# trasmissores_e_receptores.net
KiCad netlist of a schematic drawn in Altium Designer
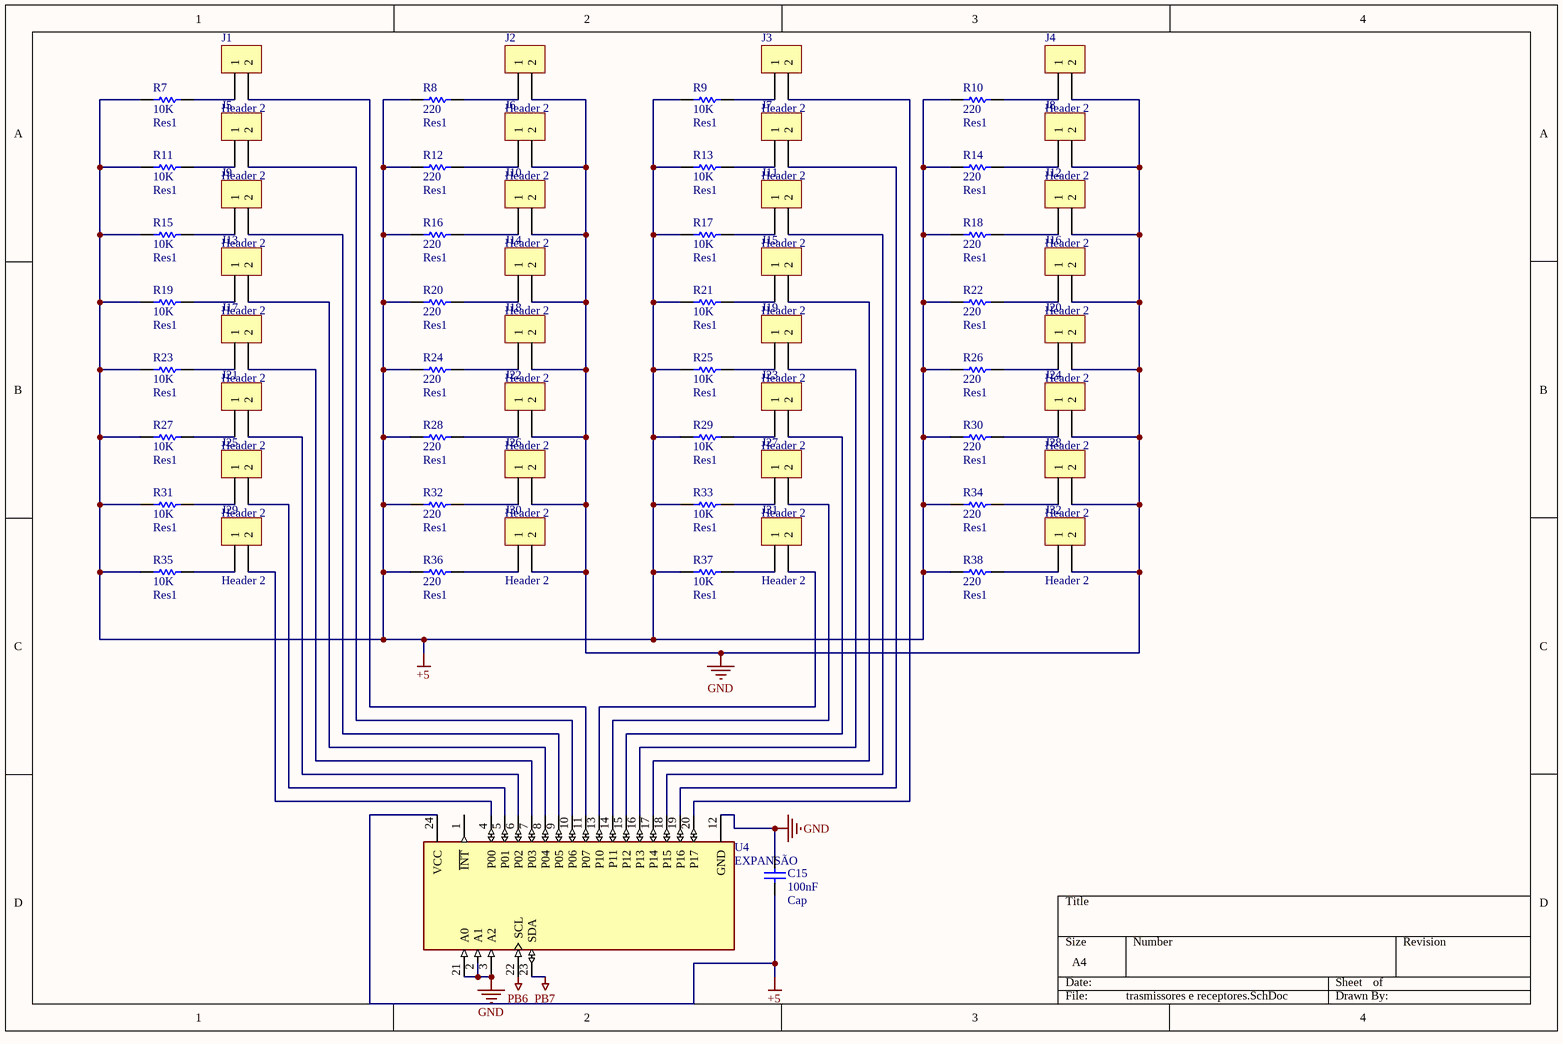
[diagram p0: trasmissores e receptores.SchDoc]

(export (version "E")
  (design (tool "Eeschema 10.0.6"))
  (components
    (comp (ref "C15")
      (value "Cap")
      (footprint "lib_footprint_projeto:CAP100N")
      (description "Capacitor")
      (fields (field (name "ALTIUM_VALUE") "100nF") (field (name "PUBLISHER") "Altium Limited"))
      (libsource (lib "Miscellaneous Devices") (part "Cap"))
    )
    (comp (ref "J1")
      (value "Header 2")
      (footprint "lib_footprint_projeto:Header_KK_2vias")
      (description "Conn KK 2 vias")
      (fields (field (name "PUBLISHER") "Altium Limited"))
      (libsource (lib "projeto_pi_3b") (part "Header 2"))
    )
    (comp (ref "J2")
      (value "Header 2")
      (footprint "lib_footprint_projeto:Header_KK_2vias")
      (description "Conn KK 2 vias")
      (fields (field (name "PUBLISHER") "Altium Limited"))
      (libsource (lib "projeto_pi_3b") (part "Header 2"))
    )
    (comp (ref "J3")
      (value "Header 2")
      (footprint "lib_footprint_projeto:Header_KK_2vias")
      (description "Conn KK 2 vias")
      (fields (field (name "PUBLISHER") "Altium Limited"))
      (libsource (lib "projeto_pi_3b") (part "Header 2"))
    )
    (comp (ref "J4")
      (value "Header 2")
      (footprint "lib_footprint_projeto:Header_KK_2vias")
      (description "Conn KK 2 vias")
      (fields (field (name "PUBLISHER") "Altium Limited"))
      (libsource (lib "projeto_pi_3b") (part "Header 2"))
    )
    (comp (ref "J5")
      (value "Header 2")
      (footprint "lib_footprint_projeto:Header_KK_2vias")
      (description "Conn KK 2 vias")
      (fields (field (name "PUBLISHER") "Altium Limited"))
      (libsource (lib "projeto_pi_3b") (part "Header 2"))
    )
    (comp (ref "J6")
      (value "Header 2")
      (footprint "lib_footprint_projeto:Header_KK_2vias")
      (description "Conn KK 2 vias")
      (fields (field (name "PUBLISHER") "Altium Limited"))
      (libsource (lib "projeto_pi_3b") (part "Header 2"))
    )
    (comp (ref "J7")
      (value "Header 2")
      (footprint "lib_footprint_projeto:Header_KK_2vias")
      (description "Conn KK 2 vias")
      (fields (field (name "PUBLISHER") "Altium Limited"))
      (libsource (lib "projeto_pi_3b") (part "Header 2"))
    )
    (comp (ref "J8")
      (value "Header 2")
      (footprint "lib_footprint_projeto:Header_KK_2vias")
      (description "Conn KK 2 vias")
      (fields (field (name "PUBLISHER") "Altium Limited"))
      (libsource (lib "projeto_pi_3b") (part "Header 2"))
    )
    (comp (ref "J9")
      (value "Header 2")
      (footprint "lib_footprint_projeto:Header_KK_2vias")
      (description "Conn KK 2 vias")
      (fields (field (name "PUBLISHER") "Altium Limited"))
      (libsource (lib "projeto_pi_3b") (part "Header 2"))
    )
    (comp (ref "J10")
      (value "Header 2")
      (footprint "lib_footprint_projeto:Header_KK_2vias")
      (description "Conn KK 2 vias")
      (fields (field (name "PUBLISHER") "Altium Limited"))
      (libsource (lib "projeto_pi_3b") (part "Header 2"))
    )
    (comp (ref "J11")
      (value "Header 2")
      (footprint "lib_footprint_projeto:Header_KK_2vias")
      (description "Conn KK 2 vias")
      (fields (field (name "PUBLISHER") "Altium Limited"))
      (libsource (lib "projeto_pi_3b") (part "Header 2"))
    )
    (comp (ref "J12")
      (value "Header 2")
      (footprint "lib_footprint_projeto:Header_KK_2vias")
      (description "Conn KK 2 vias")
      (fields (field (name "PUBLISHER") "Altium Limited"))
      (libsource (lib "projeto_pi_3b") (part "Header 2"))
    )
    (comp (ref "J13")
      (value "Header 2")
      (footprint "lib_footprint_projeto:Header_KK_2vias")
      (description "Conn KK 2 vias")
      (fields (field (name "PUBLISHER") "Altium Limited"))
      (libsource (lib "projeto_pi_3b") (part "Header 2"))
    )
    (comp (ref "J14")
      (value "Header 2")
      (footprint "lib_footprint_projeto:Header_KK_2vias")
      (description "Conn KK 2 vias")
      (fields (field (name "PUBLISHER") "Altium Limited"))
      (libsource (lib "projeto_pi_3b") (part "Header 2"))
    )
    (comp (ref "J15")
      (value "Header 2")
      (footprint "lib_footprint_projeto:Header_KK_2vias")
      (description "Conn KK 2 vias")
      (fields (field (name "PUBLISHER") "Altium Limited"))
      (libsource (lib "projeto_pi_3b") (part "Header 2"))
    )
    (comp (ref "J16")
      (value "Header 2")
      (footprint "lib_footprint_projeto:Header_KK_2vias")
      (description "Conn KK 2 vias")
      (fields (field (name "PUBLISHER") "Altium Limited"))
      (libsource (lib "projeto_pi_3b") (part "Header 2"))
    )
    (comp (ref "J17")
      (value "Header 2")
      (footprint "lib_footprint_projeto:Header_KK_2vias")
      (description "Conn KK 2 vias")
      (fields (field (name "PUBLISHER") "Altium Limited"))
      (libsource (lib "projeto_pi_3b") (part "Header 2"))
    )
    (comp (ref "J18")
      (value "Header 2")
      (footprint "lib_footprint_projeto:Header_KK_2vias")
      (description "Conn KK 2 vias")
      (fields (field (name "PUBLISHER") "Altium Limited"))
      (libsource (lib "projeto_pi_3b") (part "Header 2"))
    )
    (comp (ref "J19")
      (value "Header 2")
      (footprint "lib_footprint_projeto:Header_KK_2vias")
      (description "Conn KK 2 vias")
      (fields (field (name "PUBLISHER") "Altium Limited"))
      (libsource (lib "projeto_pi_3b") (part "Header 2"))
    )
    (comp (ref "J20")
      (value "Header 2")
      (footprint "lib_footprint_projeto:Header_KK_2vias")
      (description "Conn KK 2 vias")
      (fields (field (name "PUBLISHER") "Altium Limited"))
      (libsource (lib "projeto_pi_3b") (part "Header 2"))
    )
    (comp (ref "J21")
      (value "Header 2")
      (footprint "lib_footprint_projeto:Header_KK_2vias")
      (description "Conn KK 2 vias")
      (fields (field (name "PUBLISHER") "Altium Limited"))
      (libsource (lib "projeto_pi_3b") (part "Header 2"))
    )
    (comp (ref "J22")
      (value "Header 2")
      (footprint "lib_footprint_projeto:Header_KK_2vias")
      (description "Conn KK 2 vias")
      (fields (field (name "PUBLISHER") "Altium Limited"))
      (libsource (lib "projeto_pi_3b") (part "Header 2"))
    )
    (comp (ref "J23")
      (value "Header 2")
      (footprint "lib_footprint_projeto:Header_KK_2vias")
      (description "Conn KK 2 vias")
      (fields (field (name "PUBLISHER") "Altium Limited"))
      (libsource (lib "projeto_pi_3b") (part "Header 2"))
    )
    (comp (ref "J24")
      (value "Header 2")
      (footprint "lib_footprint_projeto:Header_KK_2vias")
      (description "Conn KK 2 vias")
      (fields (field (name "PUBLISHER") "Altium Limited"))
      (libsource (lib "projeto_pi_3b") (part "Header 2"))
    )
    (comp (ref "J25")
      (value "Header 2")
      (footprint "lib_footprint_projeto:Header_KK_2vias")
      (description "Conn KK 2 vias")
      (fields (field (name "PUBLISHER") "Altium Limited"))
      (libsource (lib "projeto_pi_3b") (part "Header 2"))
    )
    (comp (ref "J26")
      (value "Header 2")
      (footprint "lib_footprint_projeto:Header_KK_2vias")
      (description "Conn KK 2 vias")
      (fields (field (name "PUBLISHER") "Altium Limited"))
      (libsource (lib "projeto_pi_3b") (part "Header 2"))
    )
    (comp (ref "J27")
      (value "Header 2")
      (footprint "lib_footprint_projeto:Header_KK_2vias")
      (description "Conn KK 2 vias")
      (fields (field (name "PUBLISHER") "Altium Limited"))
      (libsource (lib "projeto_pi_3b") (part "Header 2"))
    )
    (comp (ref "J28")
      (value "Header 2")
      (footprint "lib_footprint_projeto:Header_KK_2vias")
      (description "Conn KK 2 vias")
      (fields (field (name "PUBLISHER") "Altium Limited"))
      (libsource (lib "projeto_pi_3b") (part "Header 2"))
    )
    (comp (ref "J29")
      (value "Header 2")
      (footprint "lib_footprint_projeto:Header_KK_2vias")
      (description "Conn KK 2 vias")
      (fields (field (name "PUBLISHER") "Altium Limited"))
      (libsource (lib "projeto_pi_3b") (part "Header 2"))
    )
    (comp (ref "J30")
      (value "Header 2")
      (footprint "lib_footprint_projeto:Header_KK_2vias")
      (description "Conn KK 2 vias")
      (fields (field (name "PUBLISHER") "Altium Limited"))
      (libsource (lib "projeto_pi_3b") (part "Header 2"))
    )
    (comp (ref "J31")
      (value "Header 2")
      (footprint "lib_footprint_projeto:Header_KK_2vias")
      (description "Conn KK 2 vias")
      (fields (field (name "PUBLISHER") "Altium Limited"))
      (libsource (lib "projeto_pi_3b") (part "Header 2"))
    )
    (comp (ref "J32")
      (value "Header 2")
      (footprint "lib_footprint_projeto:Header_KK_2vias")
      (description "Conn KK 2 vias")
      (fields (field (name "PUBLISHER") "Altium Limited"))
      (libsource (lib "projeto_pi_3b") (part "Header 2"))
    )
    (comp (ref "R7")
      (value "Res1")
      (footprint "lib_footprint_projeto:RES10K")
      (description "Resistor")
      (fields (field (name "ALTIUM_VALUE") "10K") (field (name "PUBLISHER") "Altium Limited"))
      (libsource (lib "Miscellaneous Devices") (part "Res1"))
    )
    (comp (ref "R8")
      (value "Res1")
      (footprint "lib_footprint_projeto:RES220")
      (description "Resistor")
      (fields (field (name "ALTIUM_VALUE") "220") (field (name "PUBLISHER") "Altium Limited"))
      (libsource (lib "Miscellaneous Devices") (part "Res1"))
    )
    (comp (ref "R9")
      (value "Res1")
      (footprint "lib_footprint_projeto:RES10K")
      (description "Resistor")
      (fields (field (name "ALTIUM_VALUE") "10K") (field (name "PUBLISHER") "Altium Limited"))
      (libsource (lib "Miscellaneous Devices") (part "Res1"))
    )
    (comp (ref "R10")
      (value "Res1")
      (footprint "lib_footprint_projeto:RES220")
      (description "Resistor")
      (fields (field (name "ALTIUM_VALUE") "220") (field (name "PUBLISHER") "Altium Limited"))
      (libsource (lib "Miscellaneous Devices") (part "Res1"))
    )
    (comp (ref "R11")
      (value "Res1")
      (footprint "lib_footprint_projeto:RES10K")
      (description "Resistor")
      (fields (field (name "ALTIUM_VALUE") "10K") (field (name "PUBLISHER") "Altium Limited"))
      (libsource (lib "Miscellaneous Devices") (part "Res1"))
    )
    (comp (ref "R12")
      (value "Res1")
      (footprint "lib_footprint_projeto:RES220")
      (description "Resistor")
      (fields (field (name "ALTIUM_VALUE") "220") (field (name "PUBLISHER") "Altium Limited"))
      (libsource (lib "Miscellaneous Devices") (part "Res1"))
    )
    (comp (ref "R13")
      (value "Res1")
      (footprint "lib_footprint_projeto:RES10K")
      (description "Resistor")
      (fields (field (name "ALTIUM_VALUE") "10K") (field (name "PUBLISHER") "Altium Limited"))
      (libsource (lib "Miscellaneous Devices") (part "Res1"))
    )
    (comp (ref "R14")
      (value "Res1")
      (footprint "lib_footprint_projeto:RES220")
      (description "Resistor")
      (fields (field (name "ALTIUM_VALUE") "220") (field (name "PUBLISHER") "Altium Limited"))
      (libsource (lib "Miscellaneous Devices") (part "Res1"))
    )
    (comp (ref "R15")
      (value "Res1")
      (footprint "lib_footprint_projeto:RES10K")
      (description "Resistor")
      (fields (field (name "ALTIUM_VALUE") "10K") (field (name "PUBLISHER") "Altium Limited"))
      (libsource (lib "Miscellaneous Devices") (part "Res1"))
    )
    (comp (ref "R16")
      (value "Res1")
      (footprint "lib_footprint_projeto:RES220")
      (description "Resistor")
      (fields (field (name "ALTIUM_VALUE") "220") (field (name "PUBLISHER") "Altium Limited"))
      (libsource (lib "Miscellaneous Devices") (part "Res1"))
    )
    (comp (ref "R17")
      (value "Res1")
      (footprint "lib_footprint_projeto:RES10K")
      (description "Resistor")
      (fields (field (name "ALTIUM_VALUE") "10K") (field (name "PUBLISHER") "Altium Limited"))
      (libsource (lib "Miscellaneous Devices") (part "Res1"))
    )
    (comp (ref "R18")
      (value "Res1")
      (footprint "lib_footprint_projeto:RES220")
      (description "Resistor")
      (fields (field (name "ALTIUM_VALUE") "220") (field (name "PUBLISHER") "Altium Limited"))
      (libsource (lib "Miscellaneous Devices") (part "Res1"))
    )
    (comp (ref "R19")
      (value "Res1")
      (footprint "lib_footprint_projeto:RES10K")
      (description "Resistor")
      (fields (field (name "ALTIUM_VALUE") "10K") (field (name "PUBLISHER") "Altium Limited"))
      (libsource (lib "Miscellaneous Devices") (part "Res1"))
    )
    (comp (ref "R20")
      (value "Res1")
      (footprint "lib_footprint_projeto:RES220")
      (description "Resistor")
      (fields (field (name "ALTIUM_VALUE") "220") (field (name "PUBLISHER") "Altium Limited"))
      (libsource (lib "Miscellaneous Devices") (part "Res1"))
    )
    (comp (ref "R21")
      (value "Res1")
      (footprint "lib_footprint_projeto:RES10K")
      (description "Resistor")
      (fields (field (name "ALTIUM_VALUE") "10K") (field (name "PUBLISHER") "Altium Limited"))
      (libsource (lib "Miscellaneous Devices") (part "Res1"))
    )
    (comp (ref "R22")
      (value "Res1")
      (footprint "lib_footprint_projeto:RES220")
      (description "Resistor")
      (fields (field (name "ALTIUM_VALUE") "220") (field (name "PUBLISHER") "Altium Limited"))
      (libsource (lib "Miscellaneous Devices") (part "Res1"))
    )
    (comp (ref "R23")
      (value "Res1")
      (footprint "lib_footprint_projeto:RES10K")
      (description "Resistor")
      (fields (field (name "ALTIUM_VALUE") "10K") (field (name "PUBLISHER") "Altium Limited"))
      (libsource (lib "Miscellaneous Devices") (part "Res1"))
    )
    (comp (ref "R24")
      (value "Res1")
      (footprint "lib_footprint_projeto:RES220")
      (description "Resistor")
      (fields (field (name "ALTIUM_VALUE") "220") (field (name "PUBLISHER") "Altium Limited"))
      (libsource (lib "Miscellaneous Devices") (part "Res1"))
    )
    (comp (ref "R25")
      (value "Res1")
      (footprint "lib_footprint_projeto:RES10K")
      (description "Resistor")
      (fields (field (name "ALTIUM_VALUE") "10K") (field (name "PUBLISHER") "Altium Limited"))
      (libsource (lib "Miscellaneous Devices") (part "Res1"))
    )
    (comp (ref "R26")
      (value "Res1")
      (footprint "lib_footprint_projeto:RES220")
      (description "Resistor")
      (fields (field (name "ALTIUM_VALUE") "220") (field (name "PUBLISHER") "Altium Limited"))
      (libsource (lib "Miscellaneous Devices") (part "Res1"))
    )
    (comp (ref "R27")
      (value "Res1")
      (footprint "lib_footprint_projeto:RES10K")
      (description "Resistor")
      (fields (field (name "ALTIUM_VALUE") "10K") (field (name "PUBLISHER") "Altium Limited"))
      (libsource (lib "Miscellaneous Devices") (part "Res1"))
    )
    (comp (ref "R28")
      (value "Res1")
      (footprint "lib_footprint_projeto:RES220")
      (description "Resistor")
      (fields (field (name "ALTIUM_VALUE") "220") (field (name "PUBLISHER") "Altium Limited"))
      (libsource (lib "Miscellaneous Devices") (part "Res1"))
    )
    (comp (ref "R29")
      (value "Res1")
      (footprint "lib_footprint_projeto:RES10K")
      (description "Resistor")
      (fields (field (name "ALTIUM_VALUE") "10K") (field (name "PUBLISHER") "Altium Limited"))
      (libsource (lib "Miscellaneous Devices") (part "Res1"))
    )
    (comp (ref "R30")
      (value "Res1")
      (footprint "lib_footprint_projeto:RES220")
      (description "Resistor")
      (fields (field (name "ALTIUM_VALUE") "220") (field (name "PUBLISHER") "Altium Limited"))
      (libsource (lib "Miscellaneous Devices") (part "Res1"))
    )
    (comp (ref "R31")
      (value "Res1")
      (footprint "lib_footprint_projeto:RES10K")
      (description "Resistor")
      (fields (field (name "ALTIUM_VALUE") "10K") (field (name "PUBLISHER") "Altium Limited"))
      (libsource (lib "Miscellaneous Devices") (part "Res1"))
    )
    (comp (ref "R32")
      (value "Res1")
      (footprint "lib_footprint_projeto:RES220")
      (description "Resistor")
      (fields (field (name "ALTIUM_VALUE") "220") (field (name "PUBLISHER") "Altium Limited"))
      (libsource (lib "Miscellaneous Devices") (part "Res1"))
    )
    (comp (ref "R33")
      (value "Res1")
      (footprint "lib_footprint_projeto:RES10K")
      (description "Resistor")
      (fields (field (name "ALTIUM_VALUE") "10K") (field (name "PUBLISHER") "Altium Limited"))
      (libsource (lib "Miscellaneous Devices") (part "Res1"))
    )
    (comp (ref "R34")
      (value "Res1")
      (footprint "lib_footprint_projeto:RES220")
      (description "Resistor")
      (fields (field (name "ALTIUM_VALUE") "220") (field (name "PUBLISHER") "Altium Limited"))
      (libsource (lib "Miscellaneous Devices") (part "Res1"))
    )
    (comp (ref "R35")
      (value "Res1")
      (footprint "lib_footprint_projeto:RES10K")
      (description "Resistor")
      (fields (field (name "ALTIUM_VALUE") "10K") (field (name "PUBLISHER") "Altium Limited"))
      (libsource (lib "Miscellaneous Devices") (part "Res1"))
    )
    (comp (ref "R36")
      (value "Res1")
      (footprint "lib_footprint_projeto:RES220")
      (description "Resistor")
      (fields (field (name "ALTIUM_VALUE") "220") (field (name "PUBLISHER") "Altium Limited"))
      (libsource (lib "Miscellaneous Devices") (part "Res1"))
    )
    (comp (ref "R37")
      (value "Res1")
      (footprint "lib_footprint_projeto:RES10K")
      (description "Resistor")
      (fields (field (name "ALTIUM_VALUE") "10K") (field (name "PUBLISHER") "Altium Limited"))
      (libsource (lib "Miscellaneous Devices") (part "Res1"))
    )
    (comp (ref "R38")
      (value "Res1")
      (footprint "lib_footprint_projeto:RES220")
      (description "Resistor")
      (fields (field (name "ALTIUM_VALUE") "220") (field (name "PUBLISHER") "Altium Limited"))
      (libsource (lib "Miscellaneous Devices") (part "Res1"))
    )
    (comp (ref "U4")
      (value "EXPANSÃO")
      (footprint "lib_footprint_projeto:Modulo")
      (description "16-bit 2.5- to 5.5-V I2C/SMBus I/O expander with interrupt")
      (fields (field (name "MF") "Texas Instruments") (field (name "MP") "PCF8575DW"))
      (libsource (lib "projeto_pi_3b") (part "EXPANSÃO"))
    )
  )
  (nets
    (net (code "1") (name "+5") (class "Default")
      (node (ref "C15") (pin "1") (pinfunction "1_1") (pintype "passive"))
      (node (ref "R10") (pin "1") (pinfunction "1_1") (pintype "passive"))
      (node (ref "R11") (pin "1") (pinfunction "1_1") (pintype "passive"))
      (node (ref "R12") (pin "1") (pinfunction "1_1") (pintype "passive"))
      (node (ref "R13") (pin "1") (pinfunction "1_1") (pintype "passive"))
      (node (ref "R14") (pin "1") (pinfunction "1_1") (pintype "passive"))
      (node (ref "R15") (pin "1") (pinfunction "1_1") (pintype "passive"))
      (node (ref "R16") (pin "1") (pinfunction "1_1") (pintype "passive"))
      (node (ref "R17") (pin "1") (pinfunction "1_1") (pintype "passive"))
      (node (ref "R18") (pin "1") (pinfunction "1_1") (pintype "passive"))
      (node (ref "R19") (pin "1") (pinfunction "1_1") (pintype "passive"))
      (node (ref "R20") (pin "1") (pinfunction "1_1") (pintype "passive"))
      (node (ref "R21") (pin "1") (pinfunction "1_1") (pintype "passive"))
      (node (ref "R22") (pin "1") (pinfunction "1_1") (pintype "passive"))
      (node (ref "R23") (pin "1") (pinfunction "1_1") (pintype "passive"))
      (node (ref "R24") (pin "1") (pinfunction "1_1") (pintype "passive"))
      (node (ref "R25") (pin "1") (pinfunction "1_1") (pintype "passive"))
      (node (ref "R26") (pin "1") (pinfunction "1_1") (pintype "passive"))
      (node (ref "R27") (pin "1") (pinfunction "1_1") (pintype "passive"))
      (node (ref "R28") (pin "1") (pinfunction "1_1") (pintype "passive"))
      (node (ref "R29") (pin "1") (pinfunction "1_1") (pintype "passive"))
      (node (ref "R30") (pin "1") (pinfunction "1_1") (pintype "passive"))
      (node (ref "R31") (pin "1") (pinfunction "1_1") (pintype "passive"))
      (node (ref "R32") (pin "1") (pinfunction "1_1") (pintype "passive"))
      (node (ref "R33") (pin "1") (pinfunction "1_1") (pintype "passive"))
      (node (ref "R34") (pin "1") (pinfunction "1_1") (pintype "passive"))
      (node (ref "R35") (pin "1") (pinfunction "1_1") (pintype "passive"))
      (node (ref "R36") (pin "1") (pinfunction "1_1") (pintype "passive"))
      (node (ref "R37") (pin "1") (pinfunction "1_1") (pintype "passive"))
      (node (ref "R38") (pin "1") (pinfunction "1_1") (pintype "passive"))
      (node (ref "R7") (pin "1") (pinfunction "1_1") (pintype "passive"))
      (node (ref "R8") (pin "1") (pinfunction "1_1") (pintype "passive"))
      (node (ref "R9") (pin "1") (pinfunction "1_1") (pintype "passive"))
      (node (ref "U4") (pin "24") (pinfunction "VCC_24") (pintype "power_in"))
    )
    (net (code "2") (name "GND") (class "Default")
      (node (ref "C15") (pin "2") (pinfunction "2_2") (pintype "passive"))
      (node (ref "J10") (pin "2") (pinfunction "2_2") (pintype "passive"))
      (node (ref "J12") (pin "2") (pinfunction "2_2") (pintype "passive"))
      (node (ref "J14") (pin "2") (pinfunction "2_2") (pintype "passive"))
      (node (ref "J16") (pin "2") (pinfunction "2_2") (pintype "passive"))
      (node (ref "J18") (pin "2") (pinfunction "2_2") (pintype "passive"))
      (node (ref "J2") (pin "2") (pinfunction "2_2") (pintype "passive"))
      (node (ref "J20") (pin "2") (pinfunction "2_2") (pintype "passive"))
      (node (ref "J22") (pin "2") (pinfunction "2_2") (pintype "passive"))
      (node (ref "J24") (pin "2") (pinfunction "2_2") (pintype "passive"))
      (node (ref "J26") (pin "2") (pinfunction "2_2") (pintype "passive"))
      (node (ref "J28") (pin "2") (pinfunction "2_2") (pintype "passive"))
      (node (ref "J30") (pin "2") (pinfunction "2_2") (pintype "passive"))
      (node (ref "J32") (pin "2") (pinfunction "2_2") (pintype "passive"))
      (node (ref "J4") (pin "2") (pinfunction "2_2") (pintype "passive"))
      (node (ref "J6") (pin "2") (pinfunction "2_2") (pintype "passive"))
      (node (ref "J8") (pin "2") (pinfunction "2_2") (pintype "passive"))
      (node (ref "U4") (pin "12") (pinfunction "GND_12") (pintype "power_in"))
      (node (ref "U4") (pin "2") (pinfunction "A1_2") (pintype "input"))
      (node (ref "U4") (pin "21") (pinfunction "A0_21") (pintype "input"))
      (node (ref "U4") (pin "3") (pinfunction "A2_3") (pintype "input"))
    )
    (net (code "3") (name "Net-(J1-Pad1)") (class "Default")
      (node (ref "J1") (pin "1") (pinfunction "1_1") (pintype "passive"))
      (node (ref "R7") (pin "2") (pinfunction "2_2") (pintype "passive"))
    )
    (net (code "4") (name "Net-(J2-Pad1)") (class "Default")
      (node (ref "J2") (pin "1") (pinfunction "1_1") (pintype "passive"))
      (node (ref "R8") (pin "2") (pinfunction "2_2") (pintype "passive"))
    )
    (net (code "5") (name "Net-(J3-Pad1)") (class "Default")
      (node (ref "J3") (pin "1") (pinfunction "1_1") (pintype "passive"))
      (node (ref "R9") (pin "2") (pinfunction "2_2") (pintype "passive"))
    )
    (net (code "6") (name "Net-(J4-Pad1)") (class "Default")
      (node (ref "J4") (pin "1") (pinfunction "1_1") (pintype "passive"))
      (node (ref "R10") (pin "2") (pinfunction "2_2") (pintype "passive"))
    )
    (net (code "7") (name "Net-(J5-Pad1)") (class "Default")
      (node (ref "J5") (pin "1") (pinfunction "1_1") (pintype "passive"))
      (node (ref "R11") (pin "2") (pinfunction "2_2") (pintype "passive"))
    )
    (net (code "8") (name "Net-(J6-Pad1)") (class "Default")
      (node (ref "J6") (pin "1") (pinfunction "1_1") (pintype "passive"))
      (node (ref "R12") (pin "2") (pinfunction "2_2") (pintype "passive"))
    )
    (net (code "9") (name "Net-(J7-Pad1)") (class "Default")
      (node (ref "J7") (pin "1") (pinfunction "1_1") (pintype "passive"))
      (node (ref "R13") (pin "2") (pinfunction "2_2") (pintype "passive"))
    )
    (net (code "10") (name "Net-(J8-Pad1)") (class "Default")
      (node (ref "J8") (pin "1") (pinfunction "1_1") (pintype "passive"))
      (node (ref "R14") (pin "2") (pinfunction "2_2") (pintype "passive"))
    )
    (net (code "11") (name "Net-(J9-Pad1)") (class "Default")
      (node (ref "J9") (pin "1") (pinfunction "1_1") (pintype "passive"))
      (node (ref "R15") (pin "2") (pinfunction "2_2") (pintype "passive"))
    )
    (net (code "12") (name "Net-(J10-Pad1)") (class "Default")
      (node (ref "J10") (pin "1") (pinfunction "1_1") (pintype "passive"))
      (node (ref "R16") (pin "2") (pinfunction "2_2") (pintype "passive"))
    )
    (net (code "13") (name "Net-(J11-Pad1)") (class "Default")
      (node (ref "J11") (pin "1") (pinfunction "1_1") (pintype "passive"))
      (node (ref "R17") (pin "2") (pinfunction "2_2") (pintype "passive"))
    )
    (net (code "14") (name "Net-(J12-Pad1)") (class "Default")
      (node (ref "J12") (pin "1") (pinfunction "1_1") (pintype "passive"))
      (node (ref "R18") (pin "2") (pinfunction "2_2") (pintype "passive"))
    )
    (net (code "15") (name "Net-(J13-Pad1)") (class "Default")
      (node (ref "J13") (pin "1") (pinfunction "1_1") (pintype "passive"))
      (node (ref "R19") (pin "2") (pinfunction "2_2") (pintype "passive"))
    )
    (net (code "16") (name "Net-(J14-Pad1)") (class "Default")
      (node (ref "J14") (pin "1") (pinfunction "1_1") (pintype "passive"))
      (node (ref "R20") (pin "2") (pinfunction "2_2") (pintype "passive"))
    )
    (net (code "17") (name "Net-(J15-Pad1)") (class "Default")
      (node (ref "J15") (pin "1") (pinfunction "1_1") (pintype "passive"))
      (node (ref "R21") (pin "2") (pinfunction "2_2") (pintype "passive"))
    )
    (net (code "18") (name "Net-(J16-Pad1)") (class "Default")
      (node (ref "J16") (pin "1") (pinfunction "1_1") (pintype "passive"))
      (node (ref "R22") (pin "2") (pinfunction "2_2") (pintype "passive"))
    )
    (net (code "19") (name "Net-(J17-Pad1)") (class "Default")
      (node (ref "J17") (pin "1") (pinfunction "1_1") (pintype "passive"))
      (node (ref "R23") (pin "2") (pinfunction "2_2") (pintype "passive"))
    )
    (net (code "20") (name "Net-(J18-Pad1)") (class "Default")
      (node (ref "J18") (pin "1") (pinfunction "1_1") (pintype "passive"))
      (node (ref "R24") (pin "2") (pinfunction "2_2") (pintype "passive"))
    )
    (net (code "21") (name "Net-(J19-Pad1)") (class "Default")
      (node (ref "J19") (pin "1") (pinfunction "1_1") (pintype "passive"))
      (node (ref "R25") (pin "2") (pinfunction "2_2") (pintype "passive"))
    )
    (net (code "22") (name "Net-(J20-Pad1)") (class "Default")
      (node (ref "J20") (pin "1") (pinfunction "1_1") (pintype "passive"))
      (node (ref "R26") (pin "2") (pinfunction "2_2") (pintype "passive"))
    )
    (net (code "23") (name "Net-(J21-Pad1)") (class "Default")
      (node (ref "J21") (pin "1") (pinfunction "1_1") (pintype "passive"))
      (node (ref "R27") (pin "2") (pinfunction "2_2") (pintype "passive"))
    )
    (net (code "24") (name "Net-(J22-Pad1)") (class "Default")
      (node (ref "J22") (pin "1") (pinfunction "1_1") (pintype "passive"))
      (node (ref "R28") (pin "2") (pinfunction "2_2") (pintype "passive"))
    )
    (net (code "25") (name "Net-(J23-Pad1)") (class "Default")
      (node (ref "J23") (pin "1") (pinfunction "1_1") (pintype "passive"))
      (node (ref "R29") (pin "2") (pinfunction "2_2") (pintype "passive"))
    )
    (net (code "26") (name "Net-(J24-Pad1)") (class "Default")
      (node (ref "J24") (pin "1") (pinfunction "1_1") (pintype "passive"))
      (node (ref "R30") (pin "2") (pinfunction "2_2") (pintype "passive"))
    )
    (net (code "27") (name "Net-(J25-Pad1)") (class "Default")
      (node (ref "J25") (pin "1") (pinfunction "1_1") (pintype "passive"))
      (node (ref "R31") (pin "2") (pinfunction "2_2") (pintype "passive"))
    )
    (net (code "28") (name "Net-(J26-Pad1)") (class "Default")
      (node (ref "J26") (pin "1") (pinfunction "1_1") (pintype "passive"))
      (node (ref "R32") (pin "2") (pinfunction "2_2") (pintype "passive"))
    )
    (net (code "29") (name "Net-(J27-Pad1)") (class "Default")
      (node (ref "J27") (pin "1") (pinfunction "1_1") (pintype "passive"))
      (node (ref "R33") (pin "2") (pinfunction "2_2") (pintype "passive"))
    )
    (net (code "30") (name "Net-(J28-Pad1)") (class "Default")
      (node (ref "J28") (pin "1") (pinfunction "1_1") (pintype "passive"))
      (node (ref "R34") (pin "2") (pinfunction "2_2") (pintype "passive"))
    )
    (net (code "31") (name "Net-(J29-Pad1)") (class "Default")
      (node (ref "J29") (pin "1") (pinfunction "1_1") (pintype "passive"))
      (node (ref "R35") (pin "2") (pinfunction "2_2") (pintype "passive"))
    )
    (net (code "32") (name "Net-(J30-Pad1)") (class "Default")
      (node (ref "J30") (pin "1") (pinfunction "1_1") (pintype "passive"))
      (node (ref "R36") (pin "2") (pinfunction "2_2") (pintype "passive"))
    )
    (net (code "33") (name "Net-(J31-Pad1)") (class "Default")
      (node (ref "J31") (pin "1") (pinfunction "1_1") (pintype "passive"))
      (node (ref "R37") (pin "2") (pinfunction "2_2") (pintype "passive"))
    )
    (net (code "34") (name "Net-(J32-Pad1)") (class "Default")
      (node (ref "J32") (pin "1") (pinfunction "1_1") (pintype "passive"))
      (node (ref "R38") (pin "2") (pinfunction "2_2") (pintype "passive"))
    )
    (net (code "35") (name "Net-(U4-P00)") (class "Default")
      (node (ref "J29") (pin "2") (pinfunction "2_2") (pintype "passive"))
      (node (ref "U4") (pin "4") (pinfunction "P00_4") (pintype "bidirectional"))
    )
    (net (code "36") (name "Net-(U4-P01)") (class "Default")
      (node (ref "J25") (pin "2") (pinfunction "2_2") (pintype "passive"))
      (node (ref "U4") (pin "5") (pinfunction "P01_5") (pintype "bidirectional"))
    )
    (net (code "37") (name "Net-(U4-P02)") (class "Default")
      (node (ref "J21") (pin "2") (pinfunction "2_2") (pintype "passive"))
      (node (ref "U4") (pin "6") (pinfunction "P02_6") (pintype "bidirectional"))
    )
    (net (code "38") (name "Net-(U4-P03)") (class "Default")
      (node (ref "J17") (pin "2") (pinfunction "2_2") (pintype "passive"))
      (node (ref "U4") (pin "7") (pinfunction "P03_7") (pintype "bidirectional"))
    )
    (net (code "39") (name "Net-(U4-P04)") (class "Default")
      (node (ref "J13") (pin "2") (pinfunction "2_2") (pintype "passive"))
      (node (ref "U4") (pin "8") (pinfunction "P04_8") (pintype "bidirectional"))
    )
    (net (code "40") (name "Net-(U4-P05)") (class "Default")
      (node (ref "J9") (pin "2") (pinfunction "2_2") (pintype "passive"))
      (node (ref "U4") (pin "9") (pinfunction "P05_9") (pintype "bidirectional"))
    )
    (net (code "41") (name "Net-(U4-P06)") (class "Default")
      (node (ref "J5") (pin "2") (pinfunction "2_2") (pintype "passive"))
      (node (ref "U4") (pin "10") (pinfunction "P06_10") (pintype "bidirectional"))
    )
    (net (code "42") (name "Net-(U4-P07)") (class "Default")
      (node (ref "J1") (pin "2") (pinfunction "2_2") (pintype "passive"))
      (node (ref "U4") (pin "11") (pinfunction "P07_11") (pintype "bidirectional"))
    )
    (net (code "43") (name "Net-(U4-P10)") (class "Default")
      (node (ref "J31") (pin "2") (pinfunction "2_2") (pintype "passive"))
      (node (ref "U4") (pin "13") (pinfunction "P10_13") (pintype "bidirectional"))
    )
    (net (code "44") (name "Net-(U4-P11)") (class "Default")
      (node (ref "J27") (pin "2") (pinfunction "2_2") (pintype "passive"))
      (node (ref "U4") (pin "14") (pinfunction "P11_14") (pintype "bidirectional"))
    )
    (net (code "45") (name "Net-(U4-P12)") (class "Default")
      (node (ref "J23") (pin "2") (pinfunction "2_2") (pintype "passive"))
      (node (ref "U4") (pin "15") (pinfunction "P12_15") (pintype "bidirectional"))
    )
    (net (code "46") (name "Net-(U4-P13)") (class "Default")
      (node (ref "J19") (pin "2") (pinfunction "2_2") (pintype "passive"))
      (node (ref "U4") (pin "16") (pinfunction "P13_16") (pintype "bidirectional"))
    )
    (net (code "47") (name "Net-(U4-P14)") (class "Default")
      (node (ref "J15") (pin "2") (pinfunction "2_2") (pintype "passive"))
      (node (ref "U4") (pin "17") (pinfunction "P14_17") (pintype "bidirectional"))
    )
    (net (code "48") (name "Net-(U4-P15)") (class "Default")
      (node (ref "J11") (pin "2") (pinfunction "2_2") (pintype "passive"))
      (node (ref "U4") (pin "18") (pinfunction "P15_18") (pintype "bidirectional"))
    )
    (net (code "49") (name "Net-(U4-P16)") (class "Default")
      (node (ref "J7") (pin "2") (pinfunction "2_2") (pintype "passive"))
      (node (ref "U4") (pin "19") (pinfunction "P16_19") (pintype "bidirectional"))
    )
    (net (code "50") (name "Net-(U4-P17)") (class "Default")
      (node (ref "J3") (pin "2") (pinfunction "2_2") (pintype "passive"))
      (node (ref "U4") (pin "20") (pinfunction "P17_20") (pintype "bidirectional"))
    )
    (net (code "51") (name "PB6") (class "Default")
      (node (ref "U4") (pin "22") (pinfunction "SCL_22") (pintype "input"))
    )
    (net (code "52") (name "PB7") (class "Default")
      (node (ref "U4") (pin "23") (pinfunction "SDA_23") (pintype "bidirectional"))
    )
    (net (code "53") (name "unconnected-(U4-~{INT}-Pad1)") (class "Default")
      (node (ref "U4") (pin "1") (pinfunction "~{INT}_1") (pintype "output"))
    )
  )
)
